# 555flasher.net
KiCad netlist of a schematic drawn in EAGLE
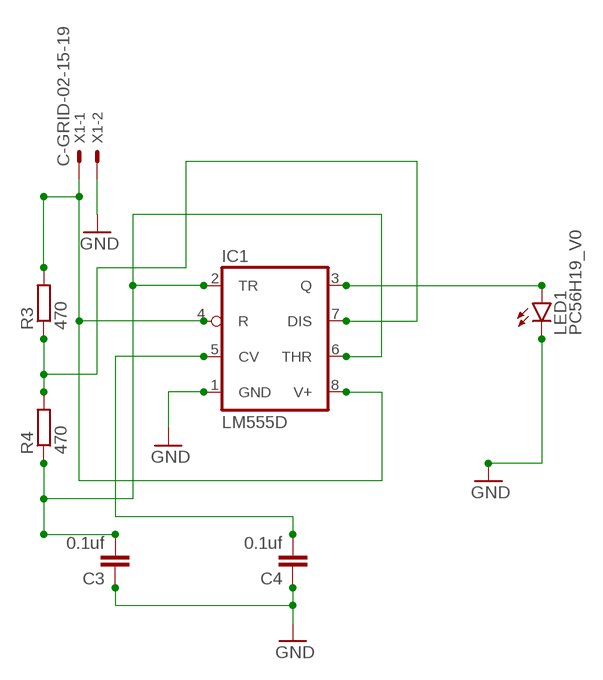
[diagram p0: schematic, sheet 1]

(export (version "E")
  (design (tool "Eeschema 10.0.6"))
  (components
    (comp (ref "C3")
      (value "0.1uf")
      (footprint "eagle-import:C0805")
      (libsource (lib "eagle-import") (part "C-EUC0805"))
    )
    (comp (ref "C4")
      (value "0.1uf")
      (footprint "eagle-import:C0805")
      (libsource (lib "eagle-import") (part "C-EUC0805"))
    )
    (comp (ref "IC1")
      (value "LM555D")
      (footprint "eagle-import:SO08")
      (libsource (lib "eagle-import") (part "555DLM"))
    )
    (comp (ref "LED1")
      (value "PC56H19_V0")
      (footprint "eagle-import:PC56H19_V0")
      (libsource (lib "eagle-import") (part "PC56H19_V0"))
    )
    (comp (ref "R3")
      (value "470")
      (footprint "eagle-import:R0805")
      (libsource (lib "eagle-import") (part "R-EU_R0805"))
    )
    (comp (ref "R4")
      (value "470")
      (footprint "eagle-import:R0805")
      (libsource (lib "eagle-import") (part "R-EU_R0805"))
    )
    (comp (ref "X1")
      (value "C-GRID-02-15-19")
      (footprint "eagle-import:15-91-02")
      (fields (field (name "MF") "MOLEX"))
      (libsource (lib "eagle-import") (part "C-GRID-02-15-19"))
    )
  )
  (nets
    (net (code "1") (name "GND") (class "Default")
      (node (ref "C3") (pin "1") (pinfunction "1_1") (pintype "passive"))
      (node (ref "C4") (pin "1") (pinfunction "1_1") (pintype "passive"))
      (node (ref "IC1") (pin "1") (pinfunction "GND_1") (pintype "power_in"))
      (node (ref "LED1") (pin "1") (pinfunction "C_1") (pintype "passive"))
      (node (ref "LED1") (pin "3") (pinfunction "C_3") (pintype "passive"))
      (node (ref "X1") (pin "2") (pinfunction "S_2") (pintype "passive"))
    )
    (net (code "2") (name "Net-(IC1-CV)") (class "Default")
      (node (ref "C4") (pin "2") (pinfunction "2_2") (pintype "passive"))
      (node (ref "IC1") (pin "5") (pinfunction "CV_5") (pintype "input"))
    )
    (net (code "3") (name "Net-(IC1-DIS)") (class "Default")
      (node (ref "IC1") (pin "7") (pinfunction "DIS_7") (pintype "input"))
      (node (ref "R3") (pin "1") (pinfunction "1_1") (pintype "passive"))
      (node (ref "R4") (pin "2") (pinfunction "2_2") (pintype "passive"))
    )
    (net (code "4") (name "Net-(IC1-Q)") (class "Default")
      (node (ref "IC1") (pin "3") (pinfunction "Q_3") (pintype "output"))
      (node (ref "LED1") (pin "2") (pinfunction "A_2") (pintype "passive"))
      (node (ref "LED1") (pin "4") (pinfunction "A_4") (pintype "passive"))
    )
    (net (code "5") (name "Net-(IC1-R)") (class "Default")
      (node (ref "IC1") (pin "4") (pinfunction "R_4") (pintype "input"))
      (node (ref "IC1") (pin "8") (pinfunction "V+_8") (pintype "power_in"))
      (node (ref "R3") (pin "2") (pinfunction "2_2") (pintype "passive"))
      (node (ref "X1") (pin "1") (pinfunction "S_1") (pintype "passive"))
    )
    (net (code "6") (name "Net-(IC1-THR)") (class "Default")
      (node (ref "C3") (pin "2") (pinfunction "2_2") (pintype "passive"))
      (node (ref "IC1") (pin "2") (pinfunction "TR_2") (pintype "input"))
      (node (ref "IC1") (pin "6") (pinfunction "THR_6") (pintype "input"))
      (node (ref "R4") (pin "1") (pinfunction "1_1") (pintype "passive"))
    )
  )
)
